# 5V_to_3_3V_regulator.net
KiCad netlist of a schematic drawn in Altium Designer
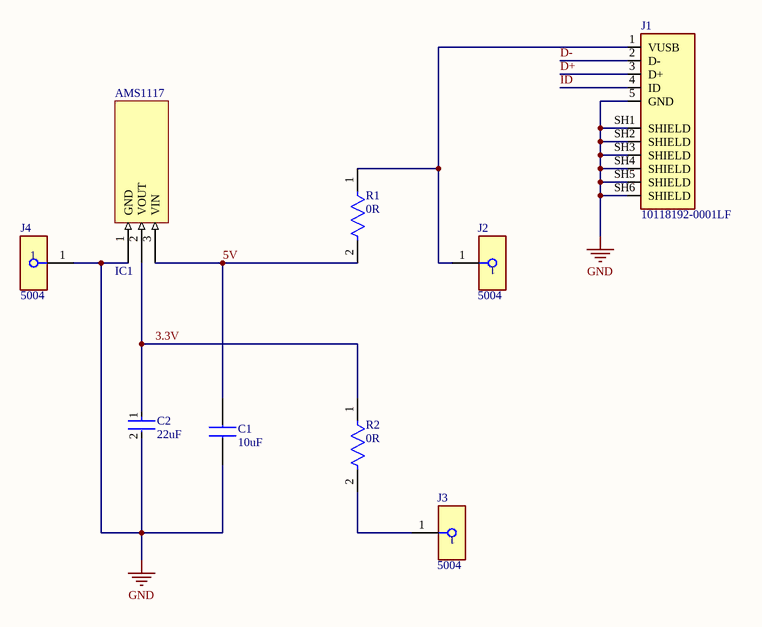
[diagram p0: 5V to 3.3V regulator.SchDoc]

(export (version "E")
  (design (tool "Eeschema 10.0.6"))
  (components
    (comp (ref "AMS1117")
      (value "IC1")
      (footprint "SOT89-150P350X150-3N")
      (fields
        (field (name "MANUFACTURER") "YONGYUTAI")
        (field (name "MFR. PART #") "AMS1117-3.3")
        (field (name "LCSC PART #") "C2904742")
      )
      (libsource (lib "AMS1117-3.3") (part "IC?"))
    )
    (comp (ref "C1")
      (value "10uF")
      (footprint "CAPC1005X70N")
      (description "6.3V 10uF X5R ±20% 0402 Multilayer Ceramic Capacitors MLCC - SMD/SMT ROHS")
      (fields
        (field (name "MANUFACTURER") "Samsung Electro-Mechanics")
        (field (name "MFR. PART #") "CL05A106MQ5NUNC")
      )
      (libsource (lib "CL05A106MQ5NUNC") (part "CL05A106MQ5NUNC"))
    )
    (comp (ref "C2")
      (value "22uF")
      (footprint "FP-GRM219-0_2-0_15-IPC_A")
      (description "Chip Multilayer Ceramic Capacitors for General Purpose, 0805, 22uF, X5R, 15%, 20%, 16V")
      (fields (field (name "MFR. PART #") "GRM219R61C226ME15L") (field (name "LCSC PART #") "C162295"))
      (libsource (lib "Altium Content Vault") (part "b4654b650e69147ec39a6b967a45e02"))
    )
    (comp (ref "J1")
      (value "10118192-0001LF")
      (footprint "AMPHENOL_10118192-0001LF")
      (description "Single Port 5 Contact Horizontal Right Angle Shielded Micro B USB 2.0 Connector")
      (libsource (lib "10118192-0001LF") (part "10118192-0001LF"))
    )
    (comp (ref "J2")
      (value "5004")
      (footprint "FP-5004-MFG")
      (description "PC TEST POINT MINIATURE YELLOW")
      (fields (field (name "MANUFACTURER") "Keystone") (field (name "LCSC PART #") "C2906762"))
      (libsource (lib "") (part "98815daf2f2c152b0c43f5ab9800df6_1"))
    )
    (comp (ref "J3")
      (value "5004")
      (footprint "FP-5004-MFG")
      (description "PC TEST POINT MINIATURE YELLOW")
      (fields (field (name "MANUFACTURER") "Keystone") (field (name "LCSC PART #") "C2906762"))
      (libsource (lib "") (part "98815daf2f2c152b0c43f5ab9800df6_1"))
    )
    (comp (ref "J4")
      (value "5004")
      (footprint "FP-5004-MFG")
      (description "PC TEST POINT MINIATURE YELLOW")
      (fields (field (name "MANUFACTURER") "Keystone") (field (name "LCSC PART #") "C2906762"))
      (libsource (lib "Altium Content Vault") (part "98815daf2f2c152b0c43f5ab9800df6"))
    )
    (comp (ref "R1")
      (value "0R")
      (footprint "FP-RC0402-0_4-IPC_A")
      (description "RES SMD 0 OHM JUMPER 1/16W 0402")
      (fields (field (name "MANUFACTURER") "Yageo") (field (name "LCSC PART #") "C106231"))
      (libsource (lib "Altium Content Vault") (part "1029c3af85768c4190bb7ad29bc67b5"))
    )
    (comp (ref "R2")
      (value "0R")
      (footprint "FP-RC0402-0_4-IPC_A")
      (description "RES SMD 0 OHM JUMPER 1/16W 0402")
      (fields (field (name "MANUFACTURER") "Yageo") (field (name "LCSC PART #") "C106231"))
      (libsource (lib "Altium Content Vault") (part "1029c3af85768c4190bb7ad29bc67b5"))
    )
  )
  (nets
    (net (code "1") (name "/3.3V") (class "Default")
      (node (ref "AMS1117") (pin "2") (pinfunction "VOUT_2") (pintype "input"))
      (node (ref "C2") (pin "1") (pinfunction "1_1") (pintype "passive"))
      (node (ref "R2") (pin "1") (pinfunction "1_1") (pintype "passive"))
    )
    (net (code "2") (name "/5V") (class "Default")
      (node (ref "AMS1117") (pin "3") (pinfunction "VIN_3") (pintype "input"))
      (node (ref "C1") (pin "2") (pinfunction "2_2") (pintype "passive"))
      (node (ref "R1") (pin "2") (pinfunction "2_2") (pintype "passive"))
    )
    (net (code "3") (name "/D+") (class "Default")
      (node (ref "J1") (pin "3") (pinfunction "D+_3") (pintype "passive"))
    )
    (net (code "4") (name "/D-") (class "Default")
      (node (ref "J1") (pin "2") (pinfunction "D-_2") (pintype "passive"))
    )
    (net (code "5") (name "/ID") (class "Default")
      (node (ref "J1") (pin "4") (pinfunction "ID_4") (pintype "passive"))
    )
    (net (code "6") (name "GND") (class "Default")
      (node (ref "AMS1117") (pin "1") (pinfunction "GND_1") (pintype "input"))
      (node (ref "C1") (pin "1") (pinfunction "1_1") (pintype "passive"))
      (node (ref "C2") (pin "2") (pinfunction "2_2") (pintype "passive"))
      (node (ref "J1") (pin "5") (pinfunction "GND_5") (pintype "passive"))
      (node (ref "J1") (pin "SH1") (pinfunction "SHIELD_SH1") (pintype "passive"))
      (node (ref "J1") (pin "SH2") (pinfunction "SHIELD_SH2") (pintype "passive"))
      (node (ref "J1") (pin "SH3") (pinfunction "SHIELD_SH3") (pintype "passive"))
      (node (ref "J1") (pin "SH4") (pinfunction "SHIELD_SH4") (pintype "passive"))
      (node (ref "J1") (pin "SH5") (pinfunction "SHIELD_SH5") (pintype "passive"))
      (node (ref "J1") (pin "SH6") (pinfunction "SHIELD_SH6") (pintype "passive"))
      (node (ref "J4") (pin "1") (pinfunction "1_1") (pintype "passive"))
    )
    (net (code "7") (name "Net-(J1-VUSB)") (class "Default")
      (node (ref "J1") (pin "1") (pinfunction "VUSB_1") (pintype "passive"))
      (node (ref "J2") (pin "1") (pinfunction "1_1") (pintype "passive"))
      (node (ref "R1") (pin "1") (pinfunction "1_1") (pintype "passive"))
    )
    (net (code "8") (name "Net-(J3-Pad1)") (class "Default")
      (node (ref "J3") (pin "1") (pinfunction "1_1") (pintype "passive"))
      (node (ref "R2") (pin "2") (pinfunction "2_2") (pintype "passive"))
    )
  )
)
